# zumo_cc.net
KiCad netlist of a schematic drawn in EAGLE
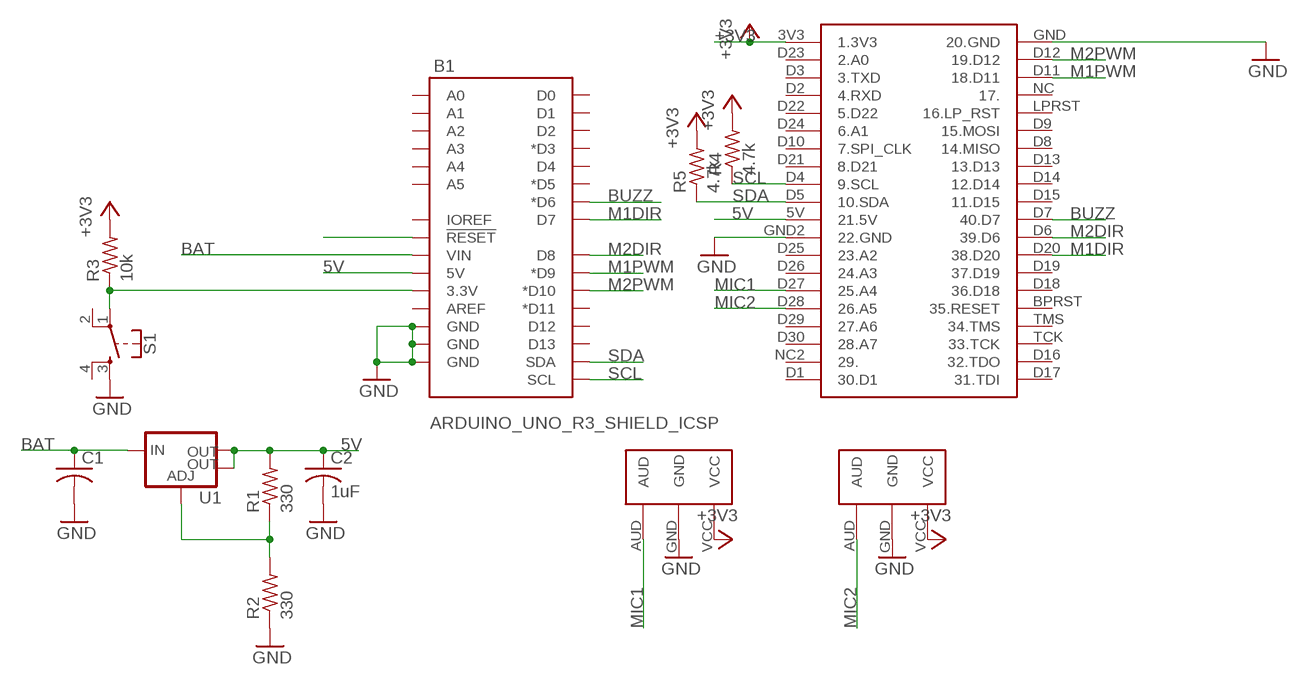
[diagram p0: schematic, sheet 1]

(export (version "E")
  (design (tool "Eeschema 10.0.6"))
  (components
    (comp (ref "B1")
      (value "ARDUINO_UNO_R3_SHIELD_ICSP")
      (footprint "eagle-import:UNO_R3_SHIELD_ICSP")
      (libsource (lib "eagle-import") (part "ARDUINO_UNO_R3_SHIELD_ICSP"))
    )
    (comp (ref "C1")
      (value "1uF")
      (footprint "eagle-import:C0603")
      (libsource (lib "eagle-import") (part "C-USC0603"))
    )
    (comp (ref "C2")
      (value "1uF")
      (footprint "eagle-import:C0603")
      (libsource (lib "eagle-import") (part "C-USC0603"))
    )
    (comp (ref "R1")
      (value "330")
      (footprint "eagle-import:R0603")
      (libsource (lib "eagle-import") (part "R-US_R0603"))
    )
    (comp (ref "R2")
      (value "330")
      (footprint "eagle-import:R0603")
      (libsource (lib "eagle-import") (part "R-US_R0603"))
    )
    (comp (ref "R3")
      (value "10k")
      (footprint "eagle-import:R0603")
      (libsource (lib "eagle-import") (part "R-US_R0603"))
    )
    (comp (ref "R4")
      (value "4.7k")
      (footprint "eagle-import:R0603")
      (libsource (lib "eagle-import") (part "R-US_R0603"))
    )
    (comp (ref "R5")
      (value "4.7k")
      (footprint "eagle-import:R0603")
      (libsource (lib "eagle-import") (part "R-US_R0603"))
    )
    (comp (ref "S1")
      (value "MOMENTARY-SWITCH-SPST-2-SMD-5.2MM")
      (footprint "eagle-import:TACTILE_SWITCH_SMD_5.2MM")
      (libsource (lib "eagle-import") (part "MOMENTARY-SWITCH-SPST-2-SMD-5.2MM"))
    )
    (comp (ref "U$1")
      (value "CC1310_INT")
      (footprint "eagle-import:CC1310_INT")
      (libsource (lib "eagle-import") (part "CC1310_INT"))
    )
    (comp (ref "U$2")
      (value "ANALOG_MIC")
      (footprint "eagle-import:ANALOG_MIC")
      (libsource (lib "eagle-import") (part "ANALOG_MIC"))
    )
    (comp (ref "U$3")
      (value "ANALOG_MIC")
      (footprint "eagle-import:ANALOG_MIC")
      (libsource (lib "eagle-import") (part "ANALOG_MIC"))
    )
    (comp (ref "U1")
      (value "NU32V7_V_REG_LM1117SOT223")
      (footprint "eagle-import:NU32V7_SOT223")
      (libsource (lib "eagle-import") (part "NU32V7_V_REG_LM1117SOT223"))
    )
  )
  (nets
    (net (code "1") (name "+3V3") (class "Default")
      (node (ref "R3") (pin "2") (pinfunction "2_2") (pintype "passive"))
      (node (ref "R4") (pin "2") (pinfunction "2_2") (pintype "passive"))
      (node (ref "R5") (pin "2") (pinfunction "2_2") (pintype "passive"))
      (node (ref "U$1") (pin "3V3") (pinfunction "1.3V3_3V3") (pintype "bidirectional"))
      (node (ref "U$2") (pin "VCC") (pinfunction "VCC_VCC") (pintype "bidirectional"))
      (node (ref "U$3") (pin "VCC") (pinfunction "VCC_VCC") (pintype "bidirectional"))
    )
    (net (code "2") (name "/5V") (class "Default")
      (node (ref "B1") (pin "5V") (pinfunction "5V_5V") (pintype "bidirectional"))
      (node (ref "C2") (pin "1") (pinfunction "1_1") (pintype "passive"))
      (node (ref "R1") (pin "2") (pinfunction "2_2") (pintype "passive"))
      (node (ref "U$1") (pin "5V") (pinfunction "21.5V_5V") (pintype "bidirectional"))
      (node (ref "U1") (pin "OUTPUT") (pinfunction "OUT_OUTPUT") (pintype "output"))
      (node (ref "U1") (pin "VOUT") (pinfunction "OUT_VOUT") (pintype "output"))
    )
    (net (code "3") (name "/BAT") (class "Default")
      (node (ref "B1") (pin "VIN") (pinfunction "VIN_VIN") (pintype "bidirectional"))
      (node (ref "C1") (pin "1") (pinfunction "1_1") (pintype "passive"))
      (node (ref "U1") (pin "INPUT") (pinfunction "IN_INPUT") (pintype "input"))
    )
    (net (code "4") (name "/BUZZ") (class "Default")
      (node (ref "B1") (pin "D6") (pinfunction "*D6_D6") (pintype "bidirectional"))
      (node (ref "U$1") (pin "D7") (pinfunction "40.D7_D7") (pintype "bidirectional"))
    )
    (net (code "5") (name "/M1DIR") (class "Default")
      (node (ref "B1") (pin "D7") (pinfunction "D7_D7") (pintype "bidirectional"))
      (node (ref "U$1") (pin "D20") (pinfunction "38.D20_D20") (pintype "bidirectional"))
    )
    (net (code "6") (name "/M1PWM") (class "Default")
      (node (ref "B1") (pin "D9") (pinfunction "*D9_D9") (pintype "bidirectional"))
      (node (ref "U$1") (pin "D11") (pinfunction "18.D11_D11") (pintype "bidirectional"))
    )
    (net (code "7") (name "/M2DIR") (class "Default")
      (node (ref "B1") (pin "D8") (pinfunction "D8_D8") (pintype "bidirectional"))
      (node (ref "U$1") (pin "D6") (pinfunction "39.D6_D6") (pintype "bidirectional"))
    )
    (net (code "8") (name "/M2PWM") (class "Default")
      (node (ref "B1") (pin "D10") (pinfunction "*D10_D10") (pintype "bidirectional"))
      (node (ref "U$1") (pin "D12") (pinfunction "19.D12_D12") (pintype "bidirectional"))
    )
    (net (code "9") (name "/MIC1") (class "Default")
      (node (ref "U$1") (pin "D27") (pinfunction "25.A4_D27") (pintype "bidirectional"))
      (node (ref "U$2") (pin "AUD") (pinfunction "AUD_AUD") (pintype "bidirectional"))
    )
    (net (code "10") (name "/MIC2") (class "Default")
      (node (ref "U$1") (pin "D28") (pinfunction "26.A5_D28") (pintype "bidirectional"))
      (node (ref "U$3") (pin "AUD") (pinfunction "AUD_AUD") (pintype "bidirectional"))
    )
    (net (code "11") (name "/SCL") (class "Default")
      (node (ref "B1") (pin "SCL") (pinfunction "SCL_SCL") (pintype "bidirectional"))
      (node (ref "R4") (pin "1") (pinfunction "1_1") (pintype "passive"))
      (node (ref "U$1") (pin "D4") (pinfunction "9.SCL_D4") (pintype "bidirectional"))
    )
    (net (code "12") (name "/SDA") (class "Default")
      (node (ref "B1") (pin "SDA") (pinfunction "SDA_SDA") (pintype "bidirectional"))
      (node (ref "R5") (pin "1") (pinfunction "1_1") (pintype "passive"))
      (node (ref "U$1") (pin "D5") (pinfunction "10.SDA_D5") (pintype "bidirectional"))
    )
    (net (code "13") (name "GND") (class "Default")
      (node (ref "B1") (pin "GND@0") (pinfunction "GND_GND@0") (pintype "bidirectional"))
      (node (ref "B1") (pin "GND@1") (pinfunction "GND_GND@1") (pintype "bidirectional"))
      (node (ref "B1") (pin "GND@2") (pinfunction "GND_GND@2") (pintype "bidirectional"))
      (node (ref "C1") (pin "2") (pinfunction "2_2") (pintype "passive"))
      (node (ref "C2") (pin "2") (pinfunction "2_2") (pintype "passive"))
      (node (ref "R2") (pin "1") (pinfunction "1_1") (pintype "passive"))
      (node (ref "S1") (pin "3") (pinfunction "3_3") (pintype "passive"))
      (node (ref "U$1") (pin "GND") (pinfunction "20.GND_GND") (pintype "bidirectional"))
      (node (ref "U$1") (pin "GND2") (pinfunction "22.GND_GND2") (pintype "bidirectional"))
      (node (ref "U$2") (pin "GND") (pinfunction "GND_GND") (pintype "bidirectional"))
      (node (ref "U$3") (pin "GND") (pinfunction "GND_GND") (pintype "bidirectional"))
    )
    (net (code "14") (name "Net-(B1-Pad3.3V)") (class "Default")
      (node (ref "B1") (pin "3.3V") (pinfunction "3.3V_3.3V") (pintype "bidirectional"))
      (node (ref "R3") (pin "1") (pinfunction "1_1") (pintype "passive"))
      (node (ref "S1") (pin "1") (pinfunction "1_1") (pintype "passive"))
    )
    (net (code "15") (name "Net-(U1-ADJ)") (class "Default")
      (node (ref "R1") (pin "1") (pinfunction "1_1") (pintype "passive"))
      (node (ref "R2") (pin "2") (pinfunction "2_2") (pintype "passive"))
      (node (ref "U1") (pin "GND") (pinfunction "ADJ_GND") (pintype "input"))
    )
    (net (code "16") (name "unconnected-(B1-*D3-PadD3)") (class "Default")
      (node (ref "B1") (pin "D3") (pinfunction "*D3_D3") (pintype "bidirectional"))
    )
    (net (code "17") (name "unconnected-(B1-*D5-PadD5)") (class "Default")
      (node (ref "B1") (pin "D5") (pinfunction "*D5_D5") (pintype "bidirectional"))
    )
    (net (code "18") (name "unconnected-(B1-*D11-PadD11)") (class "Default")
      (node (ref "B1") (pin "D11") (pinfunction "*D11_D11") (pintype "bidirectional"))
    )
    (net (code "19") (name "unconnected-(B1-D0-PadRX)") (class "Default")
      (node (ref "B1") (pin "RX") (pinfunction "D0_RX") (pintype "bidirectional"))
    )
    (net (code "20") (name "unconnected-(B1-D1-PadTX)") (class "Default")
      (node (ref "B1") (pin "TX") (pinfunction "D1_TX") (pintype "bidirectional"))
    )
    (net (code "21") (name "unconnected-(B1-PadA0)") (class "Default")
      (node (ref "B1") (pin "A0") (pinfunction "A0_A0") (pintype "bidirectional"))
    )
    (net (code "22") (name "unconnected-(B1-PadA1)") (class "Default")
      (node (ref "B1") (pin "A1") (pinfunction "A1_A1") (pintype "bidirectional"))
    )
    (net (code "23") (name "unconnected-(B1-PadA2)") (class "Default")
      (node (ref "B1") (pin "A2") (pinfunction "A2_A2") (pintype "bidirectional"))
    )
    (net (code "24") (name "unconnected-(B1-PadA3)") (class "Default")
      (node (ref "B1") (pin "A3") (pinfunction "A3_A3") (pintype "bidirectional"))
    )
    (net (code "25") (name "unconnected-(B1-PadA4)") (class "Default")
      (node (ref "B1") (pin "A4") (pinfunction "A4_A4") (pintype "bidirectional"))
    )
    (net (code "26") (name "unconnected-(B1-PadA5)") (class "Default")
      (node (ref "B1") (pin "A5") (pinfunction "A5_A5") (pintype "bidirectional"))
    )
    (net (code "27") (name "unconnected-(B1-PadAREF)") (class "Default")
      (node (ref "B1") (pin "AREF") (pinfunction "AREF_AREF") (pintype "bidirectional"))
    )
    (net (code "28") (name "unconnected-(B1-PadD2)") (class "Default")
      (node (ref "B1") (pin "D2") (pinfunction "D2_D2") (pintype "bidirectional"))
    )
    (net (code "29") (name "unconnected-(B1-PadD4)") (class "Default")
      (node (ref "B1") (pin "D4") (pinfunction "D4_D4") (pintype "bidirectional"))
    )
    (net (code "30") (name "unconnected-(B1-PadD12)") (class "Default")
      (node (ref "B1") (pin "D12") (pinfunction "D12_D12") (pintype "bidirectional"))
    )
    (net (code "31") (name "unconnected-(B1-PadD13)") (class "Default")
      (node (ref "B1") (pin "D13") (pinfunction "D13_D13") (pintype "bidirectional"))
    )
    (net (code "32") (name "unconnected-(B1-PadIOREF)") (class "Default")
      (node (ref "B1") (pin "IOREF") (pinfunction "IOREF_IOREF") (pintype "bidirectional"))
    )
    (net (code "33") (name "unconnected-(B1-~{RESET}-PadRES)") (class "Default")
      (node (ref "B1") (pin "RES") (pinfunction "~{RESET}_RES") (pintype "bidirectional"))
    )
    (net (code "34") (name "unconnected-(S1-Pad2)") (class "Default")
      (node (ref "S1") (pin "2") (pinfunction "2_2") (pintype "passive"))
    )
    (net (code "35") (name "unconnected-(S1-Pad4)") (class "Default")
      (node (ref "S1") (pin "4") (pinfunction "4_4") (pintype "passive"))
    )
    (net (code "36") (name "unconnected-(U$1-2.A0-PadD23)") (class "Default")
      (node (ref "U$1") (pin "D23") (pinfunction "2.A0_D23") (pintype "bidirectional"))
    )
    (net (code "37") (name "unconnected-(U$1-3.TXD-PadD3)") (class "Default")
      (node (ref "U$1") (pin "D3") (pinfunction "3.TXD_D3") (pintype "bidirectional"))
    )
    (net (code "38") (name "unconnected-(U$1-4.RXD-PadD2)") (class "Default")
      (node (ref "U$1") (pin "D2") (pinfunction "4.RXD_D2") (pintype "bidirectional"))
    )
    (net (code "39") (name "unconnected-(U$1-5.D22-PadD22)") (class "Default")
      (node (ref "U$1") (pin "D22") (pinfunction "5.D22_D22") (pintype "bidirectional"))
    )
    (net (code "40") (name "unconnected-(U$1-6.A1-PadD24)") (class "Default")
      (node (ref "U$1") (pin "D24") (pinfunction "6.A1_D24") (pintype "bidirectional"))
    )
    (net (code "41") (name "unconnected-(U$1-7.SPI_CLK-PadD10)") (class "Default")
      (node (ref "U$1") (pin "D10") (pinfunction "7.SPI_CLK_D10") (pintype "bidirectional"))
    )
    (net (code "42") (name "unconnected-(U$1-8.D21-PadD21)") (class "Default")
      (node (ref "U$1") (pin "D21") (pinfunction "8.D21_D21") (pintype "bidirectional"))
    )
    (net (code "43") (name "unconnected-(U$1-11.D15-PadD15)") (class "Default")
      (node (ref "U$1") (pin "D15") (pinfunction "11.D15_D15") (pintype "bidirectional"))
    )
    (net (code "44") (name "unconnected-(U$1-12.D14-PadD14)") (class "Default")
      (node (ref "U$1") (pin "D14") (pinfunction "12.D14_D14") (pintype "bidirectional"))
    )
    (net (code "45") (name "unconnected-(U$1-13.D13-PadD13)") (class "Default")
      (node (ref "U$1") (pin "D13") (pinfunction "13.D13_D13") (pintype "bidirectional"))
    )
    (net (code "46") (name "unconnected-(U$1-14.MISO-PadD8)") (class "Default")
      (node (ref "U$1") (pin "D8") (pinfunction "14.MISO_D8") (pintype "bidirectional"))
    )
    (net (code "47") (name "unconnected-(U$1-15.MOSI-PadD9)") (class "Default")
      (node (ref "U$1") (pin "D9") (pinfunction "15.MOSI_D9") (pintype "bidirectional"))
    )
    (net (code "48") (name "unconnected-(U$1-16.LP_RST-PadLPRST)") (class "Default")
      (node (ref "U$1") (pin "LPRST") (pinfunction "16.LP_RST_LPRST") (pintype "bidirectional"))
    )
    (net (code "49") (name "unconnected-(U$1-17.-PadNC)") (class "Default")
      (node (ref "U$1") (pin "NC") (pinfunction "17._NC") (pintype "bidirectional"))
    )
    (net (code "50") (name "unconnected-(U$1-23.A2-PadD25)") (class "Default")
      (node (ref "U$1") (pin "D25") (pinfunction "23.A2_D25") (pintype "bidirectional"))
    )
    (net (code "51") (name "unconnected-(U$1-24.A3-PadD26)") (class "Default")
      (node (ref "U$1") (pin "D26") (pinfunction "24.A3_D26") (pintype "bidirectional"))
    )
    (net (code "52") (name "unconnected-(U$1-27.A6-PadD29)") (class "Default")
      (node (ref "U$1") (pin "D29") (pinfunction "27.A6_D29") (pintype "bidirectional"))
    )
    (net (code "53") (name "unconnected-(U$1-28.A7-PadD30)") (class "Default")
      (node (ref "U$1") (pin "D30") (pinfunction "28.A7_D30") (pintype "bidirectional"))
    )
    (net (code "54") (name "unconnected-(U$1-29.-PadNC2)") (class "Default")
      (node (ref "U$1") (pin "NC2") (pinfunction "29._NC2") (pintype "bidirectional"))
    )
    (net (code "55") (name "unconnected-(U$1-30.D1-PadD1)") (class "Default")
      (node (ref "U$1") (pin "D1") (pinfunction "30.D1_D1") (pintype "bidirectional"))
    )
    (net (code "56") (name "unconnected-(U$1-31.TDI-PadD17)") (class "Default")
      (node (ref "U$1") (pin "D17") (pinfunction "31.TDI_D17") (pintype "bidirectional"))
    )
    (net (code "57") (name "unconnected-(U$1-32.TDO-PadD16)") (class "Default")
      (node (ref "U$1") (pin "D16") (pinfunction "32.TDO_D16") (pintype "bidirectional"))
    )
    (net (code "58") (name "unconnected-(U$1-33.TCK-PadTCK)") (class "Default")
      (node (ref "U$1") (pin "TCK") (pinfunction "33.TCK_TCK") (pintype "bidirectional"))
    )
    (net (code "59") (name "unconnected-(U$1-34.TMS-PadTMS)") (class "Default")
      (node (ref "U$1") (pin "TMS") (pinfunction "34.TMS_TMS") (pintype "bidirectional"))
    )
    (net (code "60") (name "unconnected-(U$1-35.RESET-PadBPRST)") (class "Default")
      (node (ref "U$1") (pin "BPRST") (pinfunction "35.RESET_BPRST") (pintype "bidirectional"))
    )
    (net (code "61") (name "unconnected-(U$1-36.D18-PadD18)") (class "Default")
      (node (ref "U$1") (pin "D18") (pinfunction "36.D18_D18") (pintype "bidirectional"))
    )
    (net (code "62") (name "unconnected-(U$1-37.D19-PadD19)") (class "Default")
      (node (ref "U$1") (pin "D19") (pinfunction "37.D19_D19") (pintype "bidirectional"))
    )
  )
)
